# PSU.net
KiCad netlist of a schematic drawn in Altium Designer
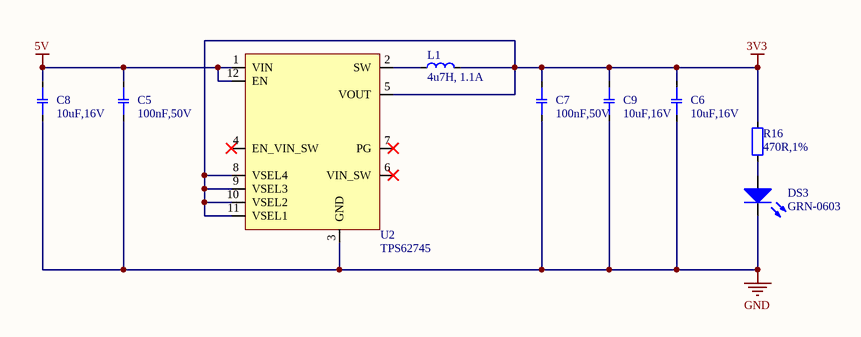
[diagram p0: PSU.SchDoc]

(export (version "E")
  (design (tool "Eeschema 10.0.6"))
  (components
    (comp (ref "C5")
      (value "100nF,50V")
      (footprint "CAPC1608X09N_0603")
      (description "CAP CER 0.1UF 50V 10% X7R 0603")
      (fields (field (name "MANUFACTURER") "Kemet") (field (name "TOLERANCE") "10%"))
      (libsource (lib "library") (part "CAP-NP_1"))
    )
    (comp (ref "C6")
      (value "10uF,16V")
      (footprint "CAPC2012X12N_0805")
      (description "CAP CER 10µF ±10% 16V X7R 0805")
      (fields
        (field (name "MANUFACTURER") "Samsung Electro-Mechanics America, Inc.")
        (field (name "TOLERANCE") "10%")
      )
      (libsource (lib "library") (part "CAP-NP_1"))
    )
    (comp (ref "C7")
      (value "100nF,50V")
      (footprint "CAPC1608X09N_0603")
      (description "CAP CER 0.1UF 50V 10% X7R 0603")
      (fields (field (name "MANUFACTURER") "Kemet") (field (name "TOLERANCE") "10%"))
      (libsource (lib "library") (part "CAP-NP_1"))
    )
    (comp (ref "C8")
      (value "10uF,16V")
      (footprint "CAPC2012X12N_0805")
      (description "CAP CER 10µF ±10% 16V X7R 0805")
      (fields
        (field (name "MANUFACTURER") "Samsung Electro-Mechanics America, Inc.")
        (field (name "TOLERANCE") "10%")
      )
      (libsource (lib "library") (part "CAP-NP_1"))
    )
    (comp (ref "C9")
      (value "10uF,16V")
      (footprint "CAPC2012X12N_0805")
      (description "CAP CER 10µF ±10% 16V X7R 0805")
      (fields
        (field (name "MANUFACTURER") "Samsung Electro-Mechanics America, Inc.")
        (field (name "TOLERANCE") "10%")
      )
      (libsource (lib "library") (part "CAP-NP_1"))
    )
    (comp (ref "DS3")
      (value "GRN-0603")
      (footprint "LED_SML-LX0603")
      (description "LED GREEN CLEAR 0603 SMD")
      (fields
        (field (name "MANUFACTURER") "Dialight")
        (field (name "MANUFACTURER PART NUMBER") "5988081107F")
      )
      (libsource (lib "library") (part "LED_1"))
    )
    (comp (ref "L1")
      (value "4u7H, 1.1A")
      (footprint "INDC2520X12N_1008")
      (description "INDUCTOR POWER 4.7UH 1.1A SMD")
      (fields
        (field (name "MANUFACTURER") "Murata Electronics North America")
        (field (name "MANUFACTURER PART NUMBER") "DFE252010R-H-4R7M=P2")
      )
      (libsource (lib "library") (part "INDUCTOR_1"))
    )
    (comp (ref "R16")
      (value "470R,1%")
      (footprint "RESC1608X06N_0603")
      (description "RES 470 OHM 1/10W 1% 0603 SMD")
      (fields (field (name "MANUFACTURER") "Rohm Semiconductor") (field (name "POWER") "0.1W"))
      (libsource (lib "library") (part "RESISTOR_1"))
    )
    (comp (ref "U2")
      (value "TPS62745")
      (footprint "R-PWSON-N12")
      (description "Step Down Converter")
      (fields (field (name "MANUFACTURER") "Texas Instruments"))
      (libsource (lib "library") (part "TPS62745"))
    )
  )
  (nets
    (net (code "1") (name "3V3") (class "Default")
      (node (ref "C6") (pin "2") (pinfunction "2_2") (pintype "passive"))
      (node (ref "C7") (pin "2") (pinfunction "2_2") (pintype "passive"))
      (node (ref "C9") (pin "2") (pinfunction "2_2") (pintype "passive"))
      (node (ref "L1") (pin "2") (pinfunction "2_2") (pintype "passive"))
      (node (ref "R16") (pin "2") (pinfunction "2_2") (pintype "passive"))
      (node (ref "U2") (pin "10") (pinfunction "VSEL2_10") (pintype "passive"))
      (node (ref "U2") (pin "11") (pinfunction "VSEL1_11") (pintype "passive"))
      (node (ref "U2") (pin "5") (pinfunction "VOUT_5") (pintype "passive"))
      (node (ref "U2") (pin "8") (pinfunction "VSEL4_8") (pintype "passive"))
      (node (ref "U2") (pin "9") (pinfunction "VSEL3_9") (pintype "passive"))
    )
    (net (code "2") (name "5V") (class "Default")
      (node (ref "C5") (pin "2") (pinfunction "2_2") (pintype "passive"))
      (node (ref "C8") (pin "2") (pinfunction "2_2") (pintype "passive"))
      (node (ref "U2") (pin "1") (pinfunction "VIN_1") (pintype "passive"))
      (node (ref "U2") (pin "12") (pinfunction "EN_12") (pintype "passive"))
    )
    (net (code "3") (name "GND") (class "Default")
      (node (ref "C5") (pin "1") (pinfunction "1_1") (pintype "passive"))
      (node (ref "C6") (pin "1") (pinfunction "1_1") (pintype "passive"))
      (node (ref "C7") (pin "1") (pinfunction "1_1") (pintype "passive"))
      (node (ref "C8") (pin "1") (pinfunction "1_1") (pintype "passive"))
      (node (ref "C9") (pin "1") (pinfunction "1_1") (pintype "passive"))
      (node (ref "DS3") (pin "1") (pinfunction "C_1") (pintype "passive"))
      (node (ref "U2") (pin "3") (pinfunction "GND_3") (pintype "passive"))
    )
    (net (code "4") (name "Net-(DS3-A)") (class "Default")
      (node (ref "DS3") (pin "2") (pinfunction "A_2") (pintype "passive"))
      (node (ref "R16") (pin "1") (pinfunction "1_1") (pintype "passive"))
    )
    (net (code "5") (name "Net-(U2-SW)") (class "Default")
      (node (ref "L1") (pin "1") (pinfunction "1_1") (pintype "passive"))
      (node (ref "U2") (pin "2") (pinfunction "SW_2") (pintype "passive"))
    )
    (net (code "6") (name "unconnected-(U2-EN_VIN_SW-Pad4)") (class "Default")
      (node (ref "U2") (pin "4") (pinfunction "EN_VIN_SW_4") (pintype "passive+no_connect"))
    )
    (net (code "7") (name "unconnected-(U2-PG-Pad7)") (class "Default")
      (node (ref "U2") (pin "7") (pinfunction "PG_7") (pintype "passive+no_connect"))
    )
    (net (code "8") (name "unconnected-(U2-VIN_SW-Pad6)") (class "Default")
      (node (ref "U2") (pin "6") (pinfunction "VIN_SW_6") (pintype "passive+no_connect"))
    )
  )
)
